# windvane_v2.net
KiCad netlist of a schematic drawn in EAGLE
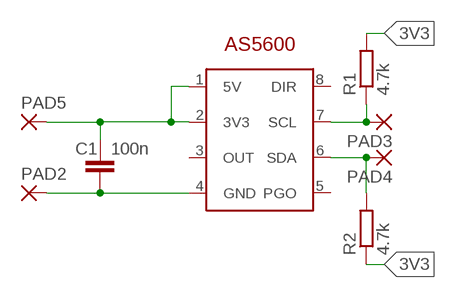
[diagram p0: schematic, sheet 1]

(export (version "E")
  (design (tool "Eeschema 10.0.6"))
  (components
    (comp (ref "C1")
      (value "100n")
      (footprint "eagle-import:C1206")
      (libsource (lib "eagle-import") (part "C-EUC1206"))
    )
    (comp (ref "PAD2")
      (value "1,6/0,8")
      (footprint "eagle-import:1,6_0,8")
      (libsource (lib "eagle-import") (part "1,6/0,8"))
    )
    (comp (ref "PAD3")
      (value "1,6/0,8")
      (footprint "eagle-import:1,6_0,8")
      (libsource (lib "eagle-import") (part "1,6/0,8"))
    )
    (comp (ref "PAD4")
      (value "1,6/0,8")
      (footprint "eagle-import:1,6_0,8")
      (libsource (lib "eagle-import") (part "1,6/0,8"))
    )
    (comp (ref "PAD5")
      (value "1,6/0,8")
      (footprint "eagle-import:1,6_0,8")
      (libsource (lib "eagle-import") (part "1,6/0,8"))
    )
    (comp (ref "R1")
      (value "4.7k")
      (footprint "eagle-import:R1206")
      (libsource (lib "eagle-import") (part "R-EU_R1206"))
    )
    (comp (ref "R2")
      (value "4.7k")
      (footprint "eagle-import:R1206")
      (libsource (lib "eagle-import") (part "R-EU_R1206"))
    )
    (comp (ref "U$1")
      (value "AS5600")
      (footprint "eagle-import:SOIC127P600X175-8N")
      (libsource (lib "eagle-import") (part "AS5600"))
    )
  )
  (nets
    (net (code "1") (name "3V3") (class "Default")
      (node (ref "C1") (pin "1") (pinfunction "1_1") (pintype "passive"))
      (node (ref "PAD5") (pin "1") (pinfunction "P_1") (pintype "passive"))
      (node (ref "R1") (pin "2") (pinfunction "2_2") (pintype "passive"))
      (node (ref "R2") (pin "1") (pinfunction "1_1") (pintype "passive"))
      (node (ref "U$1") (pin "1") (pinfunction "5V_1") (pintype "bidirectional"))
      (node (ref "U$1") (pin "2") (pinfunction "3V3_2") (pintype "bidirectional"))
    )
    (net (code "2") (name "Net-(PAD2-P)") (class "Default")
      (node (ref "C1") (pin "2") (pinfunction "2_2") (pintype "passive"))
      (node (ref "PAD2") (pin "1") (pinfunction "P_1") (pintype "passive"))
      (node (ref "U$1") (pin "4") (pinfunction "GND_4") (pintype "bidirectional"))
    )
    (net (code "3") (name "Net-(PAD3-P)") (class "Default")
      (node (ref "PAD3") (pin "1") (pinfunction "P_1") (pintype "passive"))
      (node (ref "R1") (pin "1") (pinfunction "1_1") (pintype "passive"))
      (node (ref "U$1") (pin "7") (pinfunction "SCL_7") (pintype "bidirectional"))
    )
    (net (code "4") (name "Net-(PAD4-P)") (class "Default")
      (node (ref "PAD4") (pin "1") (pinfunction "P_1") (pintype "passive"))
      (node (ref "R2") (pin "2") (pinfunction "2_2") (pintype "passive"))
      (node (ref "U$1") (pin "6") (pinfunction "SDA_6") (pintype "bidirectional"))
    )
    (net (code "5") (name "unconnected-(U$1-DIR-Pad8)") (class "Default")
      (node (ref "U$1") (pin "8") (pinfunction "DIR_8") (pintype "bidirectional"))
    )
    (net (code "6") (name "unconnected-(U$1-OUT-Pad3)") (class "Default")
      (node (ref "U$1") (pin "3") (pinfunction "OUT_3") (pintype "bidirectional"))
    )
    (net (code "7") (name "unconnected-(U$1-PGO-Pad5)") (class "Default")
      (node (ref "U$1") (pin "5") (pinfunction "PGO_5") (pintype "bidirectional"))
    )
  )
)
